# wifi_Shield_V1_1.net
KiCad netlist of a schematic drawn in EAGLE
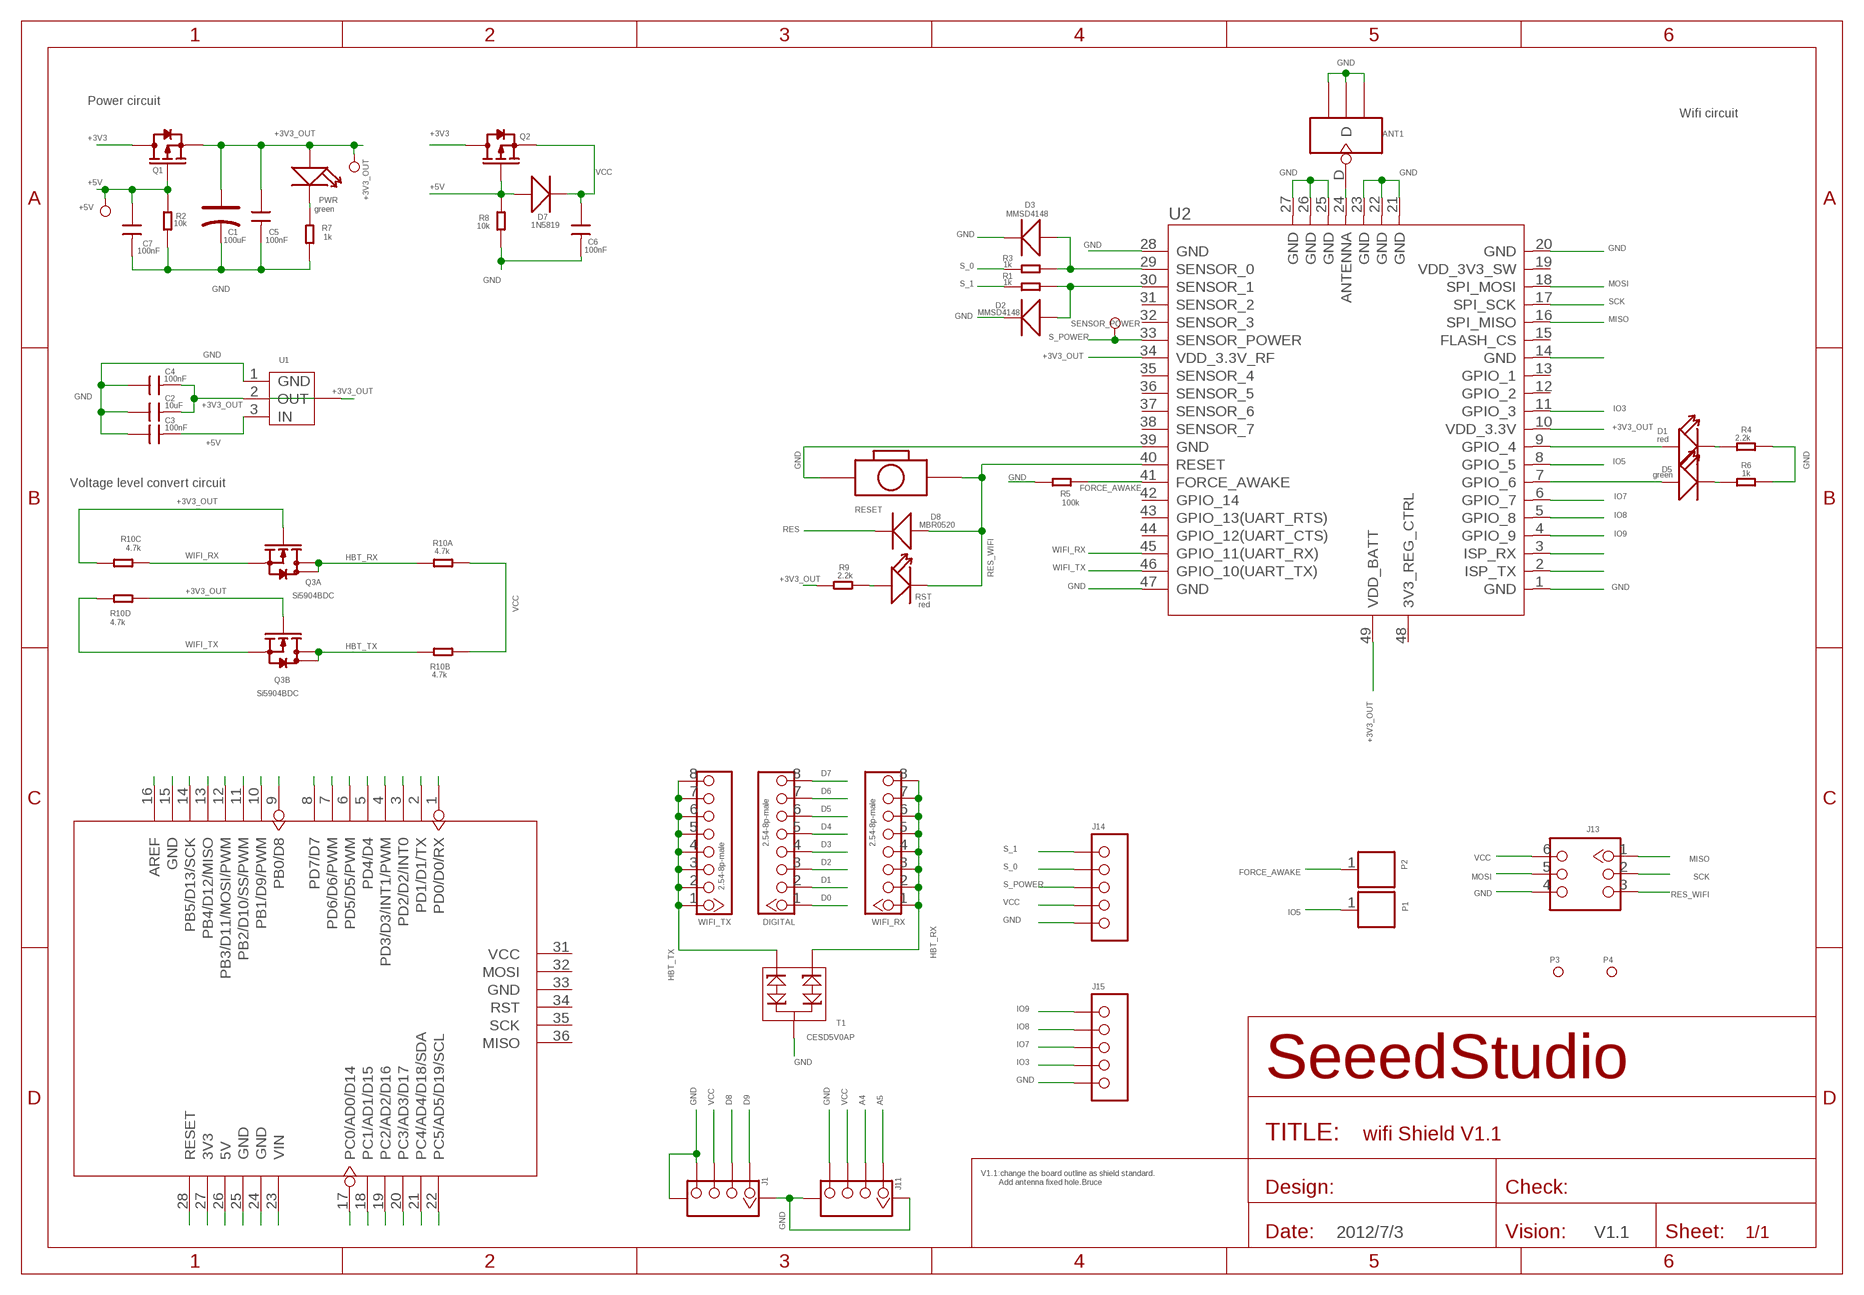
[diagram p0: schematic, sheet 1]

(export (version "E")
  (design (tool "Eeschema 10.0.6"))
  (components
    (comp (ref "+3V3_OUT")
      (value "PAD-TEST-POINT-CIRCLE_SIZE_3030")
      (footprint "eagle-import:TP_3535")
      (libsource (lib "eagle-import") (part "PAD-TEST-POINT-CIRCLE_SIZE_3030"))
    )
    (comp (ref "+5V")
      (value "PAD-TEST-POINT-CIRCLE_SIZE_3030")
      (footprint "eagle-import:TP_3535")
      (libsource (lib "eagle-import") (part "PAD-TEST-POINT-CIRCLE_SIZE_3030"))
    )
    (comp (ref "ANT1")
      (value "ANTENNA-U-FL")
      (footprint "eagle-import:4P-U-FL")
      (libsource (lib "eagle-import") (part "ANTENNA-U-FL"))
    )
    (comp (ref "C1")
      (value "100uF")
      (footprint "eagle-import:AVX-B")
      (libsource (lib "eagle-import") (part "CAP-AVX-B"))
    )
    (comp (ref "C2")
      (value "10uF")
      (footprint "eagle-import:0603")
      (libsource (lib "eagle-import") (part "C-0603"))
    )
    (comp (ref "C3")
      (value "100nF")
      (footprint "eagle-import:0603")
      (libsource (lib "eagle-import") (part "C-0603"))
    )
    (comp (ref "C4")
      (value "100nF")
      (footprint "eagle-import:0603")
      (libsource (lib "eagle-import") (part "C-0603"))
    )
    (comp (ref "C5")
      (value "100nF")
      (footprint "eagle-import:0603")
      (libsource (lib "eagle-import") (part "C-0603"))
    )
    (comp (ref "C6")
      (value "100nF")
      (footprint "eagle-import:0603")
      (libsource (lib "eagle-import") (part "C-0603"))
    )
    (comp (ref "C7")
      (value "100nF")
      (footprint "eagle-import:0603")
      (libsource (lib "eagle-import") (part "C-0603"))
    )
    (comp (ref "D1")
      (value "red")
      (footprint "eagle-import:LED-0603")
      (libsource (lib "eagle-import") (part "LED'0603'"))
    )
    (comp (ref "D2")
      (value "MMSD4148")
      (footprint "eagle-import:SOD123-2.7X1.6")
      (libsource (lib "eagle-import") (part "D-MBR0520LT1"))
    )
    (comp (ref "D3")
      (value "MMSD4148")
      (footprint "eagle-import:SOD123-2.7X1.6")
      (libsource (lib "eagle-import") (part "D-MBR0520LT1"))
    )
    (comp (ref "D5")
      (value "green")
      (footprint "eagle-import:LED-0603")
      (libsource (lib "eagle-import") (part "LED'0603'"))
    )
    (comp (ref "D7")
      (value "1N5819")
      (footprint "eagle-import:D2010")
      (libsource (lib "eagle-import") (part "D-SMA"))
    )
    (comp (ref "D8")
      (value "MBR0520")
      (footprint "eagle-import:SOD123-2.7X1.6")
      (libsource (lib "eagle-import") (part "D-MBR0520LT1"))
    )
    (comp (ref "DIGITAL")
      (value "2.54-8p-male")
      (footprint "eagle-import:8P-2.54")
      (libsource (lib "eagle-import") (part "HEADER-8P-2.54"))
    )
    (comp (ref "J1")
      (value "TWIG-4P-2.0-SMD-FEMALE-REINFORCE'90D'")
      (footprint "eagle-import:4P-SMD-2.0-90D")
      (libsource (lib "eagle-import") (part "TWIG-4P-2.0-SMD-FEMALE-REINFORCE'90D'"))
    )
    (comp (ref "J11")
      (value "TWIG-4P-2.0-SMD-FEMALE-REINFORCE'90D'")
      (footprint "eagle-import:4P-SMD-2.0-90D")
      (libsource (lib "eagle-import") (part "TWIG-4P-2.0-SMD-FEMALE-REINFORCE'90D'"))
    )
    (comp (ref "J13")
      (value "HEADER-2X3P-2.54")
      (footprint "eagle-import:2X3P-2.54")
      (libsource (lib "eagle-import") (part "HEADER-2X3P-2.54"))
    )
    (comp (ref "J14")
      (value "HEADER-5P-2.54")
      (footprint "eagle-import:5P-2.54")
      (libsource (lib "eagle-import") (part "HEADER-5P-2.54"))
    )
    (comp (ref "J15")
      (value "HEADER-5P-2.54")
      (footprint "eagle-import:5P-2.54")
      (libsource (lib "eagle-import") (part "HEADER-5P-2.54"))
    )
    (comp (ref "P1")
      (value "PAD'60/30'")
      (footprint "eagle-import:1P-65_35MIL")
      (libsource (lib "eagle-import") (part "PAD'60/30'"))
    )
    (comp (ref "P2")
      (value "PAD'60/30'")
      (footprint "eagle-import:1P-65_35MIL")
      (libsource (lib "eagle-import") (part "PAD'60/30'"))
    )
    (comp (ref "P3")
      (value "PAD-MARK")
      (footprint "eagle-import:ROUND-MARK-1.0")
      (fields (field (name "PARTNO") "DNP"))
      (libsource (lib "eagle-import") (part "PAD-MARK"))
    )
    (comp (ref "P4")
      (value "PAD-MARK")
      (footprint "eagle-import:ROUND-MARK-1.0")
      (fields (field (name "PARTNO") "DNP"))
      (libsource (lib "eagle-import") (part "PAD-MARK"))
    )
    (comp (ref "PWR")
      (value "green")
      (footprint "eagle-import:LED-0603")
      (libsource (lib "eagle-import") (part "LED'0603'"))
    )
    (comp (ref "Q1")
      (value "MOSFET-P'SI2323CDS/SI2305DS<BR>'")
      (footprint "eagle-import:SOT23")
      (libsource (lib "eagle-import") (part "MOSFET-P'SI2323CDS/SI2305DS{lt}BR{gt}'"))
    )
    (comp (ref "Q2")
      (value "MOSFET-P'SI2323CDS/SI2305DS<BR>'")
      (footprint "eagle-import:SOT23")
      (libsource (lib "eagle-import") (part "MOSFET-P'SI2323CDS/SI2305DS{lt}BR{gt}'"))
    )
    (comp (ref "Q3")
      (value "Si5904BDC")
      (footprint "eagle-import:1206-8")
      (libsource (lib "eagle-import") (part "010-DUAL-N-MOSFET_1206-8"))
    )
    (comp (ref "R1")
      (value "1k")
      (footprint "eagle-import:0603")
      (libsource (lib "eagle-import") (part "R-0603"))
    )
    (comp (ref "R2")
      (value "10k")
      (footprint "eagle-import:0603")
      (libsource (lib "eagle-import") (part "R-0603"))
    )
    (comp (ref "R3")
      (value "1k")
      (footprint "eagle-import:0603")
      (libsource (lib "eagle-import") (part "R-0603"))
    )
    (comp (ref "R4")
      (value "2.2k")
      (footprint "eagle-import:0603")
      (libsource (lib "eagle-import") (part "R-0603"))
    )
    (comp (ref "R5")
      (value "100k")
      (footprint "eagle-import:0603")
      (libsource (lib "eagle-import") (part "R-0603"))
    )
    (comp (ref "R6")
      (value "1k")
      (footprint "eagle-import:0603")
      (libsource (lib "eagle-import") (part "R-0603"))
    )
    (comp (ref "R7")
      (value "1k")
      (footprint "eagle-import:0603")
      (libsource (lib "eagle-import") (part "R-0603"))
    )
    (comp (ref "R8")
      (value "10k")
      (footprint "eagle-import:0603")
      (libsource (lib "eagle-import") (part "R-0603"))
    )
    (comp (ref "R9")
      (value "2.2k")
      (footprint "eagle-import:0603")
      (libsource (lib "eagle-import") (part "R-0603"))
    )
    (comp (ref "R10")
      (value "4.7k")
      (footprint "eagle-import:R1206-8")
      (libsource (lib "eagle-import") (part "005-4R_1206"))
    )
    (comp (ref "RESET")
      (value "BOTTON-2P-90")
      (footprint "eagle-import:2P-7.62X3.56-90D")
      (libsource (lib "eagle-import") (part "BOTTON-2P-90"))
    )
    (comp (ref "RST")
      (value "red")
      (footprint "eagle-import:LED-0603")
      (libsource (lib "eagle-import") (part "LED'0603'"))
    )
    (comp (ref "SENSOR_POWER")
      (value "PAD-TEST-POINT-CIRCLE_SIZE_3030")
      (footprint "eagle-import:TP_3535")
      (libsource (lib "eagle-import") (part "PAD-TEST-POINT-CIRCLE_SIZE_3030"))
    )
    (comp (ref "T1")
      (value "CESD5V0AP")
      (footprint "eagle-import:SOT23")
      (libsource (lib "eagle-import") (part "D-ESD-PESDXL2BT"))
    )
    (comp (ref "U1")
      (value "LD1117SOT89")
      (footprint "eagle-import:SOT89")
      (libsource (lib "eagle-import") (part "LD1117SOT89"))
    )
    (comp (ref "U2")
      (value "WIFI-RN-171")
      (footprint "eagle-import:49P-1.27-26.67X17.78")
      (libsource (lib "eagle-import") (part "WIFI-RN-171"))
    )
    (comp (ref "U4")
      (value "ARDUINO")
      (footprint "eagle-import:ARDUINO")
      (libsource (lib "eagle-import") (part "ARDUINO"))
    )
    (comp (ref "WIFI_RX")
      (value "2.54-8p-male")
      (footprint "eagle-import:8P-2.54")
      (libsource (lib "eagle-import") (part "HEADER-8P-2.54"))
    )
    (comp (ref "WIFI_TX")
      (value "2.54-8p-male")
      (footprint "eagle-import:8P-2.54")
      (libsource (lib "eagle-import") (part "HEADER-8P-2.54"))
    )
  )
  (nets
    (net (code "1") (name "/+3V3") (class "Default")
      (node (ref "Q1") (pin "3") (pinfunction "D_3") (pintype "passive"))
      (node (ref "Q2") (pin "3") (pinfunction "D_3") (pintype "passive"))
      (node (ref "U4") (pin "27") (pinfunction "3V3_27") (pintype "bidirectional"))
    )
    (net (code "2") (name "/+3V3_OUT") (class "Default")
      (node (ref "+3V3_OUT") (pin "T") (pinfunction "T_T") (pintype "bidirectional"))
      (node (ref "C1") (pin "+") (pinfunction "+_+") (pintype "passive"))
      (node (ref "C2") (pin "2") (pinfunction "2_2") (pintype "passive"))
      (node (ref "C4") (pin "2") (pinfunction "2_2") (pintype "passive"))
      (node (ref "C5") (pin "1") (pinfunction "1_1") (pintype "passive"))
      (node (ref "PWR") (pin "+") (pinfunction "+_+") (pintype "passive"))
      (node (ref "Q1") (pin "2") (pinfunction "S_2") (pintype "passive"))
      (node (ref "Q3") (pin "2") (pinfunction "G_2") (pintype "passive"))
      (node (ref "Q3") (pin "4") (pinfunction "G_4") (pintype "passive"))
      (node (ref "R10") (pin "5") (pinfunction "2_5") (pintype "passive"))
      (node (ref "R10") (pin "6") (pinfunction "2_6") (pintype "passive"))
      (node (ref "R9") (pin "2") (pinfunction "2_2") (pintype "passive"))
      (node (ref "U1") (pin "2") (pinfunction "OUT_2") (pintype "bidirectional"))
      (node (ref "U1") (pin "4") (pinfunction "TAB_4") (pintype "bidirectional"))
      (node (ref "U2") (pin "10") (pinfunction "VDD_3.3V_10") (pintype "power_in"))
      (node (ref "U2") (pin "34") (pinfunction "VDD_3.3V_RF_34") (pintype "power_in"))
      (node (ref "U2") (pin "49") (pinfunction "VDD_BATT_49") (pintype "bidirectional"))
    )
    (net (code "3") (name "/+5V") (class "Default")
      (node (ref "+5V") (pin "T") (pinfunction "T_T") (pintype "bidirectional"))
      (node (ref "C3") (pin "2") (pinfunction "2_2") (pintype "passive"))
      (node (ref "C7") (pin "1") (pinfunction "1_1") (pintype "passive"))
      (node (ref "D7") (pin "+") (pinfunction "+_+") (pintype "passive"))
      (node (ref "Q1") (pin "1") (pinfunction "G_1") (pintype "passive"))
      (node (ref "Q2") (pin "1") (pinfunction "G_1") (pintype "passive"))
      (node (ref "R2") (pin "1") (pinfunction "1_1") (pintype "passive"))
      (node (ref "R8") (pin "1") (pinfunction "1_1") (pintype "passive"))
      (node (ref "U1") (pin "3") (pinfunction "IN_3") (pintype "bidirectional"))
      (node (ref "U4") (pin "26") (pinfunction "5V_26") (pintype "bidirectional"))
    )
    (net (code "4") (name "/A4") (class "Default")
      (node (ref "J11") (pin "2") (pinfunction "2_2") (pintype "bidirectional"))
      (node (ref "U4") (pin "21") (pinfunction "PC4/AD4/D18/SDA_21") (pintype "bidirectional"))
    )
    (net (code "5") (name "/A5") (class "Default")
      (node (ref "J11") (pin "1") (pinfunction "1_1") (pintype "bidirectional"))
      (node (ref "U4") (pin "22") (pinfunction "PC5/AD5/D19/SCL_22") (pintype "bidirectional"))
    )
    (net (code "6") (name "/D0") (class "Default")
      (node (ref "DIGITAL") (pin "1") (pinfunction "1_1") (pintype "bidirectional"))
      (node (ref "U4") (pin "1") (pinfunction "PD0/D0/RX_1") (pintype "bidirectional"))
    )
    (net (code "7") (name "/D1") (class "Default")
      (node (ref "DIGITAL") (pin "2") (pinfunction "2_2") (pintype "bidirectional"))
      (node (ref "U4") (pin "2") (pinfunction "PD1/D1/TX_2") (pintype "bidirectional"))
    )
    (net (code "8") (name "/D2") (class "Default")
      (node (ref "DIGITAL") (pin "3") (pinfunction "3_3") (pintype "bidirectional"))
      (node (ref "U4") (pin "3") (pinfunction "PD2/D2/INT0_3") (pintype "bidirectional"))
    )
    (net (code "9") (name "/D3") (class "Default")
      (node (ref "DIGITAL") (pin "4") (pinfunction "4_4") (pintype "bidirectional"))
      (node (ref "U4") (pin "4") (pinfunction "PD3/D3/INT1/PWM_4") (pintype "bidirectional"))
    )
    (net (code "10") (name "/D4") (class "Default")
      (node (ref "DIGITAL") (pin "5") (pinfunction "5_5") (pintype "bidirectional"))
      (node (ref "U4") (pin "5") (pinfunction "PD4/D4_5") (pintype "bidirectional"))
    )
    (net (code "11") (name "/D5") (class "Default")
      (node (ref "DIGITAL") (pin "6") (pinfunction "6_6") (pintype "bidirectional"))
      (node (ref "U4") (pin "6") (pinfunction "PD5/D5/PWM_6") (pintype "bidirectional"))
    )
    (net (code "12") (name "/D6") (class "Default")
      (node (ref "DIGITAL") (pin "7") (pinfunction "7_7") (pintype "bidirectional"))
      (node (ref "U4") (pin "7") (pinfunction "PD6/D6/PWM_7") (pintype "bidirectional"))
    )
    (net (code "13") (name "/D7") (class "Default")
      (node (ref "DIGITAL") (pin "8") (pinfunction "8_8") (pintype "bidirectional"))
      (node (ref "U4") (pin "8") (pinfunction "PD7/D7_8") (pintype "bidirectional"))
    )
    (net (code "14") (name "/D8") (class "Default")
      (node (ref "J1") (pin "2") (pinfunction "2_2") (pintype "bidirectional"))
      (node (ref "U4") (pin "9") (pinfunction "PB0/D8_9") (pintype "bidirectional"))
    )
    (net (code "15") (name "/D9") (class "Default")
      (node (ref "J1") (pin "1") (pinfunction "1_1") (pintype "bidirectional"))
      (node (ref "U4") (pin "10") (pinfunction "PB1/D9/PWM_10") (pintype "bidirectional"))
    )
    (net (code "16") (name "/FORCE_AWAKE") (class "Default")
      (node (ref "P2") (pin "1") (pinfunction "P$1_1") (pintype "bidirectional"))
      (node (ref "R5") (pin "1") (pinfunction "1_1") (pintype "passive"))
      (node (ref "U2") (pin "41") (pinfunction "FORCE_AWAKE_41") (pintype "bidirectional"))
    )
    (net (code "17") (name "/GND") (class "Default")
      (node (ref "ANT1") (pin "GND1") (pinfunction "GND1_GND1") (pintype "bidirectional"))
      (node (ref "ANT1") (pin "GND2") (pinfunction "GND2_GND2") (pintype "bidirectional"))
      (node (ref "ANT1") (pin "GND3") (pinfunction "GND3_GND3") (pintype "bidirectional"))
      (node (ref "C1") (pin "-") (pinfunction "-_-") (pintype "passive"))
      (node (ref "C2") (pin "1") (pinfunction "1_1") (pintype "passive"))
      (node (ref "C3") (pin "1") (pinfunction "1_1") (pintype "passive"))
      (node (ref "C4") (pin "1") (pinfunction "1_1") (pintype "passive"))
      (node (ref "C5") (pin "2") (pinfunction "2_2") (pintype "passive"))
      (node (ref "C6") (pin "2") (pinfunction "2_2") (pintype "passive"))
      (node (ref "C7") (pin "2") (pinfunction "2_2") (pintype "passive"))
      (node (ref "D2") (pin "1") (pinfunction "-_1") (pintype "passive"))
      (node (ref "D3") (pin "1") (pinfunction "-_1") (pintype "passive"))
      (node (ref "J1") (pin "4") (pinfunction "4_4") (pintype "bidirectional"))
      (node (ref "J1") (pin "SS1") (pinfunction "SS1_SS1") (pintype "bidirectional"))
      (node (ref "J1") (pin "SS2") (pinfunction "SS2_SS2") (pintype "bidirectional"))
      (node (ref "J11") (pin "4") (pinfunction "4_4") (pintype "bidirectional"))
      (node (ref "J11") (pin "SS1") (pinfunction "SS1_SS1") (pintype "bidirectional"))
      (node (ref "J11") (pin "SS2") (pinfunction "SS2_SS2") (pintype "bidirectional"))
      (node (ref "J13") (pin "4") (pinfunction "4_4") (pintype "bidirectional"))
      (node (ref "J14") (pin "5") (pinfunction "5_5") (pintype "bidirectional"))
      (node (ref "J15") (pin "5") (pinfunction "5_5") (pintype "bidirectional"))
      (node (ref "R2") (pin "2") (pinfunction "2_2") (pintype "passive"))
      (node (ref "R4") (pin "1") (pinfunction "1_1") (pintype "passive"))
      (node (ref "R5") (pin "2") (pinfunction "2_2") (pintype "passive"))
      (node (ref "R6") (pin "1") (pinfunction "1_1") (pintype "passive"))
      (node (ref "R7") (pin "1") (pinfunction "1_1") (pintype "passive"))
      (node (ref "R8") (pin "2") (pinfunction "2_2") (pintype "passive"))
      (node (ref "RESET") (pin "P$2") (pinfunction "2_P$2") (pintype "bidirectional"))
      (node (ref "T1") (pin "3") (pinfunction "3_3") (pintype "bidirectional"))
      (node (ref "U1") (pin "1") (pinfunction "GND_1") (pintype "bidirectional"))
      (node (ref "U2") (pin "1") (pinfunction "GND_1") (pintype "power_in"))
      (node (ref "U2") (pin "14") (pinfunction "GND_14") (pintype "power_in"))
      (node (ref "U2") (pin "20") (pinfunction "GND_20") (pintype "power_in"))
      (node (ref "U2") (pin "21") (pinfunction "GND_21") (pintype "power_in"))
      (node (ref "U2") (pin "22") (pinfunction "GND_22") (pintype "power_in"))
      (node (ref "U2") (pin "23") (pinfunction "GND_23") (pintype "power_in"))
      (node (ref "U2") (pin "25") (pinfunction "GND_25") (pintype "power_in"))
      (node (ref "U2") (pin "26") (pinfunction "GND_26") (pintype "power_in"))
      (node (ref "U2") (pin "27") (pinfunction "GND_27") (pintype "power_in"))
      (node (ref "U2") (pin "28") (pinfunction "GND_28") (pintype "power_in"))
      (node (ref "U2") (pin "39") (pinfunction "GND_39") (pintype "power_in"))
      (node (ref "U2") (pin "47") (pinfunction "GND_47") (pintype "power_in"))
      (node (ref "U4") (pin "15") (pinfunction "GND_15") (pintype "bidirectional"))
      (node (ref "U4") (pin "24") (pinfunction "GND_24") (pintype "bidirectional"))
      (node (ref "U4") (pin "25") (pinfunction "GND_25") (pintype "bidirectional"))
    )
    (net (code "18") (name "/HBT_RX") (class "Default")
      (node (ref "Q3") (pin "7") (pinfunction "D_7") (pintype "passive"))
      (node (ref "Q3") (pin "8") (pinfunction "D_8") (pintype "passive"))
      (node (ref "R10") (pin "1") (pinfunction "1_1") (pintype "passive"))
      (node (ref "T1") (pin "1") (pinfunction "1_1") (pintype "power_in"))
      (node (ref "WIFI_RX") (pin "1") (pinfunction "1_1") (pintype "bidirectional"))
      (node (ref "WIFI_RX") (pin "2") (pinfunction "2_2") (pintype "bidirectional"))
      (node (ref "WIFI_RX") (pin "3") (pinfunction "3_3") (pintype "bidirectional"))
      (node (ref "WIFI_RX") (pin "4") (pinfunction "4_4") (pintype "bidirectional"))
      (node (ref "WIFI_RX") (pin "5") (pinfunction "5_5") (pintype "bidirectional"))
      (node (ref "WIFI_RX") (pin "6") (pinfunction "6_6") (pintype "bidirectional"))
      (node (ref "WIFI_RX") (pin "7") (pinfunction "7_7") (pintype "bidirectional"))
      (node (ref "WIFI_RX") (pin "8") (pinfunction "8_8") (pintype "bidirectional"))
    )
    (net (code "19") (name "/HBT_TX") (class "Default")
      (node (ref "Q3") (pin "5") (pinfunction "D_5") (pintype "passive"))
      (node (ref "Q3") (pin "6") (pinfunction "D_6") (pintype "passive"))
      (node (ref "R10") (pin "2") (pinfunction "1_2") (pintype "passive"))
      (node (ref "T1") (pin "2") (pinfunction "2_2") (pintype "power_in"))
      (node (ref "WIFI_TX") (pin "1") (pinfunction "1_1") (pintype "bidirectional"))
      (node (ref "WIFI_TX") (pin "2") (pinfunction "2_2") (pintype "bidirectional"))
      (node (ref "WIFI_TX") (pin "3") (pinfunction "3_3") (pintype "bidirectional"))
      (node (ref "WIFI_TX") (pin "4") (pinfunction "4_4") (pintype "bidirectional"))
      (node (ref "WIFI_TX") (pin "5") (pinfunction "5_5") (pintype "bidirectional"))
      (node (ref "WIFI_TX") (pin "6") (pinfunction "6_6") (pintype "bidirectional"))
      (node (ref "WIFI_TX") (pin "7") (pinfunction "7_7") (pintype "bidirectional"))
      (node (ref "WIFI_TX") (pin "8") (pinfunction "8_8") (pintype "bidirectional"))
    )
    (net (code "20") (name "/IO3") (class "Default")
      (node (ref "J15") (pin "4") (pinfunction "4_4") (pintype "bidirectional"))
      (node (ref "U2") (pin "11") (pinfunction "GPIO_3_11") (pintype "bidirectional"))
    )
    (net (code "21") (name "/IO5") (class "Default")
      (node (ref "P1") (pin "1") (pinfunction "P$1_1") (pintype "bidirectional"))
      (node (ref "U2") (pin "8") (pinfunction "GPIO_5_8") (pintype "bidirectional"))
    )
    (net (code "22") (name "/IO7") (class "Default")
      (node (ref "J15") (pin "3") (pinfunction "3_3") (pintype "bidirectional"))
      (node (ref "U2") (pin "6") (pinfunction "GPIO_7_6") (pintype "bidirectional"))
    )
    (net (code "23") (name "/IO8") (class "Default")
      (node (ref "J15") (pin "2") (pinfunction "2_2") (pintype "bidirectional"))
      (node (ref "U2") (pin "5") (pinfunction "GPIO_8_5") (pintype "bidirectional"))
    )
    (net (code "24") (name "/IO9") (class "Default")
      (node (ref "J15") (pin "1") (pinfunction "1_1") (pintype "bidirectional"))
      (node (ref "U2") (pin "4") (pinfunction "GPIO_9_4") (pintype "bidirectional"))
    )
    (net (code "25") (name "/MISO") (class "Default")
      (node (ref "J13") (pin "1") (pinfunction "1_1") (pintype "bidirectional"))
      (node (ref "U2") (pin "16") (pinfunction "SPI_MISO_16") (pintype "bidirectional"))
    )
    (net (code "26") (name "/MOSI") (class "Default")
      (node (ref "J13") (pin "5") (pinfunction "5_5") (pintype "bidirectional"))
      (node (ref "U2") (pin "18") (pinfunction "SPI_MOSI_18") (pintype "bidirectional"))
    )
    (net (code "27") (name "/RES") (class "Default")
      (node (ref "D8") (pin "1") (pinfunction "-_1") (pintype "passive"))
      (node (ref "U4") (pin "28") (pinfunction "RESET_28") (pintype "bidirectional"))
    )
    (net (code "28") (name "/RES_WIFI") (class "Default")
      (node (ref "D8") (pin "2") (pinfunction "+_2") (pintype "passive"))
      (node (ref "J13") (pin "3") (pinfunction "3_3") (pintype "bidirectional"))
      (node (ref "RESET") (pin "P$1") (pinfunction "1_P$1") (pintype "bidirectional"))
      (node (ref "RST") (pin "-") (pinfunction "-_-") (pintype "passive"))
      (node (ref "U2") (pin "40") (pinfunction "RESET_40") (pintype "input"))
    )
    (net (code "29") (name "/SCK") (class "Default")
      (node (ref "J13") (pin "2") (pinfunction "2_2") (pintype "bidirectional"))
      (node (ref "U2") (pin "17") (pinfunction "SPI_SCK_17") (pintype "bidirectional"))
    )
    (net (code "30") (name "/S_0") (class "Default")
      (node (ref "J14") (pin "2") (pinfunction "2_2") (pintype "bidirectional"))
      (node (ref "R3") (pin "2") (pinfunction "2_2") (pintype "passive"))
    )
    (net (code "31") (name "/S_1") (class "Default")
      (node (ref "J14") (pin "1") (pinfunction "1_1") (pintype "bidirectional"))
      (node (ref "R1") (pin "2") (pinfunction "2_2") (pintype "passive"))
    )
    (net (code "32") (name "/S_POWER") (class "Default")
      (node (ref "J14") (pin "3") (pinfunction "3_3") (pintype "bidirectional"))
      (node (ref "SENSOR_POWER") (pin "T") (pinfunction "T_T") (pintype "bidirectional"))
      (node (ref "U2") (pin "33") (pinfunction "SENSOR_POWER_33") (pintype "output"))
    )
    (net (code "33") (name "/VCC") (class "Default")
      (node (ref "C6") (pin "1") (pinfunction "1_1") (pintype "passive"))
      (node (ref "D7") (pin "-") (pinfunction "-_-") (pintype "passive"))
      (node (ref "J1") (pin "3") (pinfunction "3_3") (pintype "bidirectional"))
      (node (ref "J11") (pin "3") (pinfunction "3_3") (pintype "bidirectional"))
      (node (ref "J13") (pin "6") (pinfunction "6_6") (pintype "bidirectional"))
      (node (ref "J14") (pin "4") (pinfunction "4_4") (pintype "bidirectional"))
      (node (ref "Q2") (pin "2") (pinfunction "S_2") (pintype "passive"))
      (node (ref "R10") (pin "7") (pinfunction "2_7") (pintype "passive"))
      (node (ref "R10") (pin "8") (pinfunction "2_8") (pintype "passive"))
    )
    (net (code "34") (name "/WIFI_RX") (class "Default")
      (node (ref "Q3") (pin "1") (pinfunction "S_1") (pintype "passive"))
      (node (ref "R10") (pin "3") (pinfunction "1_3") (pintype "passive"))
      (node (ref "U2") (pin "45") (pinfunction "GPIO_11(UART_RX)_45") (pintype "bidirectional"))
    )
    (net (code "35") (name "/WIFI_TX") (class "Default")
      (node (ref "Q3") (pin "3") (pinfunction "S_3") (pintype "passive"))
      (node (ref "R10") (pin "4") (pinfunction "1_4") (pintype "passive"))
      (node (ref "U2") (pin "46") (pinfunction "GPIO_10(UART_TX)_46") (pintype "bidirectional"))
    )
    (net (code "36") (name "Net-(D1-Pad-)") (class "Default")
      (node (ref "D1") (pin "-") (pinfunction "-_-") (pintype "passive"))
      (node (ref "R4") (pin "2") (pinfunction "2_2") (pintype "passive"))
    )
    (net (code "37") (name "Net-(D2-+)") (class "Default")
      (node (ref "D2") (pin "2") (pinfunction "+_2") (pintype "passive"))
      (node (ref "R1") (pin "1") (pinfunction "1_1") (pintype "passive"))
      (node (ref "U2") (pin "30") (pinfunction "SENSOR_1_30") (pintype "input"))
    )
    (net (code "38") (name "Net-(D3-+)") (class "Default")
      (node (ref "D3") (pin "2") (pinfunction "+_2") (pintype "passive"))
      (node (ref "R3") (pin "1") (pinfunction "1_1") (pintype "passive"))
      (node (ref "U2") (pin "29") (pinfunction "SENSOR_0_29") (pintype "input"))
    )
    (net (code "39") (name "Net-(D5-Pad-)") (class "Default")
      (node (ref "D5") (pin "-") (pinfunction "-_-") (pintype "passive"))
      (node (ref "R6") (pin "2") (pinfunction "2_2") (pintype "passive"))
    )
    (net (code "40") (name "Net-(PWR-Pad-)") (class "Default")
      (node (ref "PWR") (pin "-") (pinfunction "-_-") (pintype "passive"))
      (node (ref "R7") (pin "2") (pinfunction "2_2") (pintype "passive"))
    )
    (net (code "41") (name "Net-(R9-Pad1)") (class "Default")
      (node (ref "R9") (pin "1") (pinfunction "1_1") (pintype "passive"))
      (node (ref "RST") (pin "+") (pinfunction "+_+") (pintype "passive"))
    )
    (net (code "42") (name "Net-(U2-ANTENNA)") (class "Default")
      (node (ref "ANT1") (pin "D") (pinfunction "D_D") (pintype "bidirectional"))
      (node (ref "U2") (pin "24") (pinfunction "ANTENNA_24") (pintype "bidirectional"))
    )
    (net (code "43") (name "Net-(U2-GPIO_4)") (class "Default")
      (node (ref "D1") (pin "+") (pinfunction "+_+") (pintype "passive"))
      (node (ref "U2") (pin "9") (pinfunction "GPIO_4_9") (pintype "bidirectional"))
    )
    (net (code "44") (name "Net-(U2-GPIO_6)") (class "Default")
      (node (ref "D5") (pin "+") (pinfunction "+_+") (pintype "passive"))
      (node (ref "U2") (pin "7") (pinfunction "GPIO_6_7") (pintype "bidirectional"))
    )
    (net (code "45") (name "unconnected-(U2-3V3_REG_CTRL-Pad48)") (class "Default")
      (node (ref "U2") (pin "48") (pinfunction "3V3_REG_CTRL_48") (pintype "input"))
    )
    (net (code "46") (name "unconnected-(U2-FLASH_CS-Pad15)") (class "Default")
      (node (ref "U2") (pin "15") (pinfunction "FLASH_CS_15") (pintype "bidirectional"))
    )
    (net (code "47") (name "unconnected-(U2-GPIO_1-Pad13)") (class "Default")
      (node (ref "U2") (pin "13") (pinfunction "GPIO_1_13") (pintype "bidirectional"))
    )
    (net (code "48") (name "unconnected-(U2-GPIO_2-Pad12)") (class "Default")
      (node (ref "U2") (pin "12") (pinfunction "GPIO_2_12") (pintype "bidirectional"))
    )
    (net (code "49") (name "unconnected-(U2-GPIO_12(UART_CTS)-Pad44)") (class "Default")
      (node (ref "U2") (pin "44") (pinfunction "GPIO_12(UART_CTS)_44") (pintype "bidirectional"))
    )
    (net (code "50") (name "unconnected-(U2-GPIO_13(UART_RTS)-Pad43)") (class "Default")
      (node (ref "U2") (pin "43") (pinfunction "GPIO_13(UART_RTS)_43") (pintype "bidirectional"))
    )
    (net (code "51") (name "unconnected-(U2-GPIO_14-Pad42)") (class "Default")
      (node (ref "U2") (pin "42") (pinfunction "GPIO_14_42") (pintype "bidirectional"))
    )
    (net (code "52") (name "unconnected-(U2-ISP_RX-Pad3)") (class "Default")
      (node (ref "U2") (pin "3") (pinfunction "ISP_RX_3") (pintype "bidirectional"))
    )
    (net (code "53") (name "unconnected-(U2-ISP_TX-Pad2)") (class "Default")
      (node (ref "U2") (pin "2") (pinfunction "ISP_TX_2") (pintype "bidirectional"))
    )
    (net (code "54") (name "unconnected-(U2-SENSOR_2-Pad31)") (class "Default")
      (node (ref "U2") (pin "31") (pinfunction "SENSOR_2_31") (pintype "input"))
    )
    (net (code "55") (name "unconnected-(U2-SENSOR_3-Pad32)") (class "Default")
      (node (ref "U2") (pin "32") (pinfunction "SENSOR_3_32") (pintype "input"))
    )
    (net (code "56") (name "unconnected-(U2-SENSOR_4-Pad35)") (class "Default")
      (node (ref "U2") (pin "35") (pinfunction "SENSOR_4_35") (pintype "input"))
    )
    (net (code "57") (name "unconnected-(U2-SENSOR_5-Pad36)") (class "Default")
      (node (ref "U2") (pin "36") (pinfunction "SENSOR_5_36") (pintype "input"))
    )
    (net (code "58") (name "unconnected-(U2-SENSOR_6-Pad37)") (class "Default")
      (node (ref "U2") (pin "37") (pinfunction "SENSOR_6_37") (pintype "input"))
    )
    (net (code "59") (name "unconnected-(U2-SENSOR_7-Pad38)") (class "Default")
      (node (ref "U2") (pin "38") (pinfunction "SENSOR_7_38") (pintype "input"))
    )
    (net (code "60") (name "unconnected-(U2-VDD_3V3_SW-Pad19)") (class "Default")
      (node (ref "U2") (pin "19") (pinfunction "VDD_3V3_SW_19") (pintype "bidirectional"))
    )
    (net (code "61") (name "unconnected-(U4-AREF-Pad16)") (class "Default")
      (node (ref "U4") (pin "16") (pinfunction "AREF_16") (pintype "bidirectional"))
    )
    (net (code "62") (name "unconnected-(U4-GND-Pad33)") (class "Default")
      (node (ref "U4") (pin "33") (pinfunction "GND_33") (pintype "bidirectional"))
    )
    (net (code "63") (name "unconnected-(U4-MISO-Pad36)") (class "Default")
      (node (ref "U4") (pin "36") (pinfunction "MISO_36") (pintype "bidirectional"))
    )
    (net (code "64") (name "unconnected-(U4-MOSI-Pad32)") (class "Default")
      (node (ref "U4") (pin "32") (pinfunction "MOSI_32") (pintype "bidirectional"))
    )
    (net (code "65") (name "unconnected-(U4-PB2{slash}D10{slash}SS{slash}PWM-Pad11)") (class "Default")
      (node (ref "U4") (pin "11") (pinfunction "PB2/D10/SS/PWM_11") (pintype "bidirectional"))
    )
    (net (code "66") (name "unconnected-(U4-PB3{slash}D11{slash}MOSI{slash}PWM-Pad12)") (class "Default")
      (node (ref "U4") (pin "12") (pinfunction "PB3/D11/MOSI/PWM_12") (pintype "bidirectional"))
    )
    (net (code "67") (name "unconnected-(U4-PB4{slash}D12{slash}MISO-Pad13)") (class "Default")
      (node (ref "U4") (pin "13") (pinfunction "PB4/D12/MISO_13") (pintype "bidirectional"))
    )
    (net (code "68") (name "unconnected-(U4-PB5{slash}D13{slash}SCK-Pad14)") (class "Default")
      (node (ref "U4") (pin "14") (pinfunction "PB5/D13/SCK_14") (pintype "bidirectional"))
    )
    (net (code "69") (name "unconnected-(U4-PC0{slash}AD0{slash}D14-Pad17)") (class "Default")
      (node (ref "U4") (pin "17") (pinfunction "PC0/AD0/D14_17") (pintype "bidirectional"))
    )
    (net (code "70") (name "unconnected-(U4-PC1{slash}AD1{slash}D15-Pad18)") (class "Default")
      (node (ref "U4") (pin "18") (pinfunction "PC1/AD1/D15_18") (pintype "bidirectional"))
    )
    (net (code "71") (name "unconnected-(U4-PC2{slash}AD2{slash}D16-Pad19)") (class "Default")
      (node (ref "U4") (pin "19") (pinfunction "PC2/AD2/D16_19") (pintype "bidirectional"))
    )
    (net (code "72") (name "unconnected-(U4-PC3{slash}AD3{slash}D17-Pad20)") (class "Default")
      (node (ref "U4") (pin "20") (pinfunction "PC3/AD3/D17_20") (pintype "bidirectional"))
    )
    (net (code "73") (name "unconnected-(U4-RST-Pad34)") (class "Default")
      (node (ref "U4") (pin "34") (pinfunction "RST_34") (pintype "bidirectional"))
    )
    (net (code "74") (name "unconnected-(U4-SCK-Pad35)") (class "Default")
      (node (ref "U4") (pin "35") (pinfunction "SCK_35") (pintype "bidirectional"))
    )
    (net (code "75") (name "unconnected-(U4-VCC-Pad31)") (class "Default")
      (node (ref "U4") (pin "31") (pinfunction "VCC_31") (pintype "bidirectional"))
    )
    (net (code "76") (name "unconnected-(U4-VIN-Pad23)") (class "Default")
      (node (ref "U4") (pin "23") (pinfunction "VIN_23") (pintype "bidirectional"))
    )
  )
)
